# FuncGen_icl8038.net
KiCad netlist of a schematic drawn in EAGLE
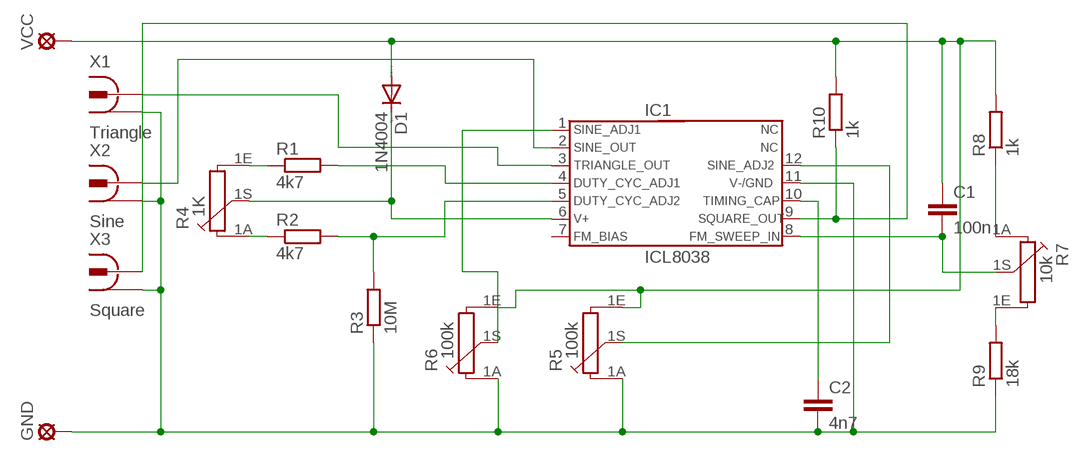
[diagram p0: schematic, sheet 1]

(export (version "E")
  (design (tool "Eeschema 10.0.6"))
  (components
    (comp (ref "C1")
      (value "100n")
      (footprint "eagle-import:C025-025X050")
      (libsource (lib "eagle-import") (part "C-EU025-025X050"))
    )
    (comp (ref "C2")
      (value "4n7")
      (footprint "eagle-import:C025-025X050")
      (libsource (lib "eagle-import") (part "C-EU025-025X050"))
    )
    (comp (ref "D1")
      (value "1N4004")
      (footprint "eagle-import:DO41-10")
      (libsource (lib "eagle-import") (part "1N4004"))
    )
    (comp (ref "GND")
      (value "LSP10")
      (footprint "eagle-import:LSP10")
      (libsource (lib "eagle-import") (part "LSP10"))
    )
    (comp (ref "IC1")
      (value "ICL8038")
      (footprint "eagle-import:ICL8038")
      (fields (field (name "MF") "Harris"))
      (libsource (lib "eagle-import") (part "ICL8038"))
    )
    (comp (ref "R1")
      (value "4k7")
      (footprint "eagle-import:0207_10")
      (libsource (lib "eagle-import") (part "R-EU_0207/10"))
    )
    (comp (ref "R2")
      (value "4k7")
      (footprint "eagle-import:0207_10")
      (libsource (lib "eagle-import") (part "R-EU_0207/10"))
    )
    (comp (ref "R3")
      (value "10M")
      (footprint "eagle-import:0207_10")
      (libsource (lib "eagle-import") (part "R-EU_0207/10"))
    )
    (comp (ref "R4")
      (value "1K")
      (footprint "eagle-import:PC16S")
      (libsource (lib "eagle-import") (part "PC16S"))
    )
    (comp (ref "R5")
      (value "100k")
      (footprint "eagle-import:PC16S")
      (libsource (lib "eagle-import") (part "PC16S"))
    )
    (comp (ref "R6")
      (value "100k")
      (footprint "eagle-import:PC16S")
      (libsource (lib "eagle-import") (part "PC16S"))
    )
    (comp (ref "R7")
      (value "10k")
      (footprint "eagle-import:PC16S")
      (libsource (lib "eagle-import") (part "PC16S"))
    )
    (comp (ref "R8")
      (value "1k")
      (footprint "eagle-import:0207_10")
      (libsource (lib "eagle-import") (part "R-EU_0207/10"))
    )
    (comp (ref "R9")
      (value "18k")
      (footprint "eagle-import:0207_10")
      (libsource (lib "eagle-import") (part "R-EU_0207/10"))
    )
    (comp (ref "R10")
      (value "1k")
      (footprint "eagle-import:0207_10")
      (libsource (lib "eagle-import") (part "R-EU_0207/10"))
    )
    (comp (ref "VCC")
      (value "LSP10")
      (footprint "eagle-import:LSP10")
      (libsource (lib "eagle-import") (part "LSP10"))
    )
    (comp (ref "X1")
      (value "Triangle")
      (footprint "eagle-import:736880-49")
      (libsource (lib "eagle-import") (part "736880-49"))
    )
    (comp (ref "X2")
      (value "Sine")
      (footprint "eagle-import:736880-49")
      (libsource (lib "eagle-import") (part "736880-49"))
    )
    (comp (ref "X3")
      (value "Square")
      (footprint "eagle-import:736880-49")
      (libsource (lib "eagle-import") (part "736880-49"))
    )
  )
  (nets
    (net (code "1") (name "Net-(C1-Pad1)") (class "Default")
      (node (ref "C1") (pin "1") (pinfunction "1_1") (pintype "passive"))
      (node (ref "D1") (pin "A") (pinfunction "A_A") (pintype "passive"))
      (node (ref "R10") (pin "2") (pinfunction "2_2") (pintype "passive"))
      (node (ref "R5") (pin "1E") (pinfunction "1E_1E") (pintype "passive"))
      (node (ref "R6") (pin "1E") (pinfunction "1E_1E") (pintype "passive"))
      (node (ref "R8") (pin "2") (pinfunction "2_2") (pintype "passive"))
      (node (ref "VCC") (pin "MP") (pinfunction "MP_MP") (pintype "passive"))
    )
    (net (code "2") (name "Net-(C1-Pad2)") (class "Default")
      (node (ref "C1") (pin "2") (pinfunction "2_2") (pintype "passive"))
      (node (ref "IC1") (pin "8") (pinfunction "8_8") (pintype "passive"))
      (node (ref "R7") (pin "1S") (pinfunction "1S_1S") (pintype "passive"))
    )
    (net (code "3") (name "Net-(C2-Pad1)") (class "Default")
      (node (ref "C2") (pin "1") (pinfunction "1_1") (pintype "passive"))
      (node (ref "IC1") (pin "10") (pinfunction "10_10") (pintype "passive"))
    )
    (net (code "4") (name "Net-(C2-Pad2)") (class "Default")
      (node (ref "C2") (pin "2") (pinfunction "2_2") (pintype "passive"))
      (node (ref "GND") (pin "MP") (pinfunction "MP_MP") (pintype "passive"))
      (node (ref "IC1") (pin "11") (pinfunction "11_11") (pintype "passive"))
      (node (ref "R3") (pin "1") (pinfunction "1_1") (pintype "passive"))
      (node (ref "R5") (pin "1A") (pinfunction "1A_1A") (pintype "passive"))
      (node (ref "R6") (pin "1A") (pinfunction "1A_1A") (pintype "passive"))
      (node (ref "R9") (pin "1") (pinfunction "1_1") (pintype "passive"))
      (node (ref "X1") (pin "1") (pinfunction "1_1") (pintype "passive"))
      (node (ref "X1") (pin "1@1") (pinfunction "1_1@1") (pintype "passive"))
      (node (ref "X1") (pin "1@2") (pinfunction "1_1@2") (pintype "passive"))
      (node (ref "X2") (pin "1") (pinfunction "1_1") (pintype "passive"))
      (node (ref "X2") (pin "1@1") (pinfunction "1_1@1") (pintype "passive"))
      (node (ref "X2") (pin "1@2") (pinfunction "1_1@2") (pintype "passive"))
      (node (ref "X3") (pin "1") (pinfunction "1_1") (pintype "passive"))
      (node (ref "X3") (pin "1@1") (pinfunction "1_1@1") (pintype "passive"))
      (node (ref "X3") (pin "1@2") (pinfunction "1_1@2") (pintype "passive"))
    )
    (net (code "5") (name "Net-(D1-PadC)") (class "Default")
      (node (ref "D1") (pin "C") (pinfunction "C_C") (pintype "passive"))
      (node (ref "IC1") (pin "6") (pinfunction "6_6") (pintype "passive"))
      (node (ref "R4") (pin "1S") (pinfunction "1S_1S") (pintype "passive"))
    )
    (net (code "6") (name "Net-(IC1-Pad1)") (class "Default")
      (node (ref "IC1") (pin "1") (pinfunction "1_1") (pintype "passive"))
      (node (ref "R6") (pin "1S") (pinfunction "1S_1S") (pintype "passive"))
    )
    (net (code "7") (name "Net-(IC1-Pad2)") (class "Default")
      (node (ref "IC1") (pin "2") (pinfunction "2_2") (pintype "passive"))
      (node (ref "X2") (pin "2") (pinfunction "2_2") (pintype "passive"))
    )
    (net (code "8") (name "Net-(IC1-Pad3)") (class "Default")
      (node (ref "IC1") (pin "3") (pinfunction "3_3") (pintype "passive"))
      (node (ref "X1") (pin "2") (pinfunction "2_2") (pintype "passive"))
    )
    (net (code "9") (name "Net-(IC1-Pad4)") (class "Default")
      (node (ref "IC1") (pin "4") (pinfunction "4_4") (pintype "passive"))
      (node (ref "R1") (pin "2") (pinfunction "2_2") (pintype "passive"))
    )
    (net (code "10") (name "Net-(IC1-Pad5)") (class "Default")
      (node (ref "IC1") (pin "5") (pinfunction "5_5") (pintype "passive"))
      (node (ref "R2") (pin "2") (pinfunction "2_2") (pintype "passive"))
      (node (ref "R3") (pin "2") (pinfunction "2_2") (pintype "passive"))
    )
    (net (code "11") (name "Net-(IC1-Pad9)") (class "Default")
      (node (ref "IC1") (pin "9") (pinfunction "9_9") (pintype "passive"))
      (node (ref "R10") (pin "1") (pinfunction "1_1") (pintype "passive"))
      (node (ref "X3") (pin "2") (pinfunction "2_2") (pintype "passive"))
    )
    (net (code "12") (name "Net-(IC1-Pad12)") (class "Default")
      (node (ref "IC1") (pin "12") (pinfunction "12_12") (pintype "passive"))
      (node (ref "R5") (pin "1S") (pinfunction "1S_1S") (pintype "passive"))
    )
    (net (code "13") (name "Net-(R1-Pad1)") (class "Default")
      (node (ref "R1") (pin "1") (pinfunction "1_1") (pintype "passive"))
      (node (ref "R4") (pin "1E") (pinfunction "1E_1E") (pintype "passive"))
    )
    (net (code "14") (name "Net-(R2-Pad1)") (class "Default")
      (node (ref "R2") (pin "1") (pinfunction "1_1") (pintype "passive"))
      (node (ref "R4") (pin "1A") (pinfunction "1A_1A") (pintype "passive"))
    )
    (net (code "15") (name "Net-(R7-Pad1A)") (class "Default")
      (node (ref "R7") (pin "1A") (pinfunction "1A_1A") (pintype "passive"))
      (node (ref "R8") (pin "1") (pinfunction "1_1") (pintype "passive"))
    )
    (net (code "16") (name "Net-(R7-Pad1E)") (class "Default")
      (node (ref "R7") (pin "1E") (pinfunction "1E_1E") (pintype "passive"))
      (node (ref "R9") (pin "2") (pinfunction "2_2") (pintype "passive"))
    )
    (net (code "17") (name "unconnected-(IC1-Pad7)") (class "Default")
      (node (ref "IC1") (pin "7") (pinfunction "7_7") (pintype "passive"))
    )
  )
)
